# LED.net
KiCad netlist of a schematic drawn in Altium Designer
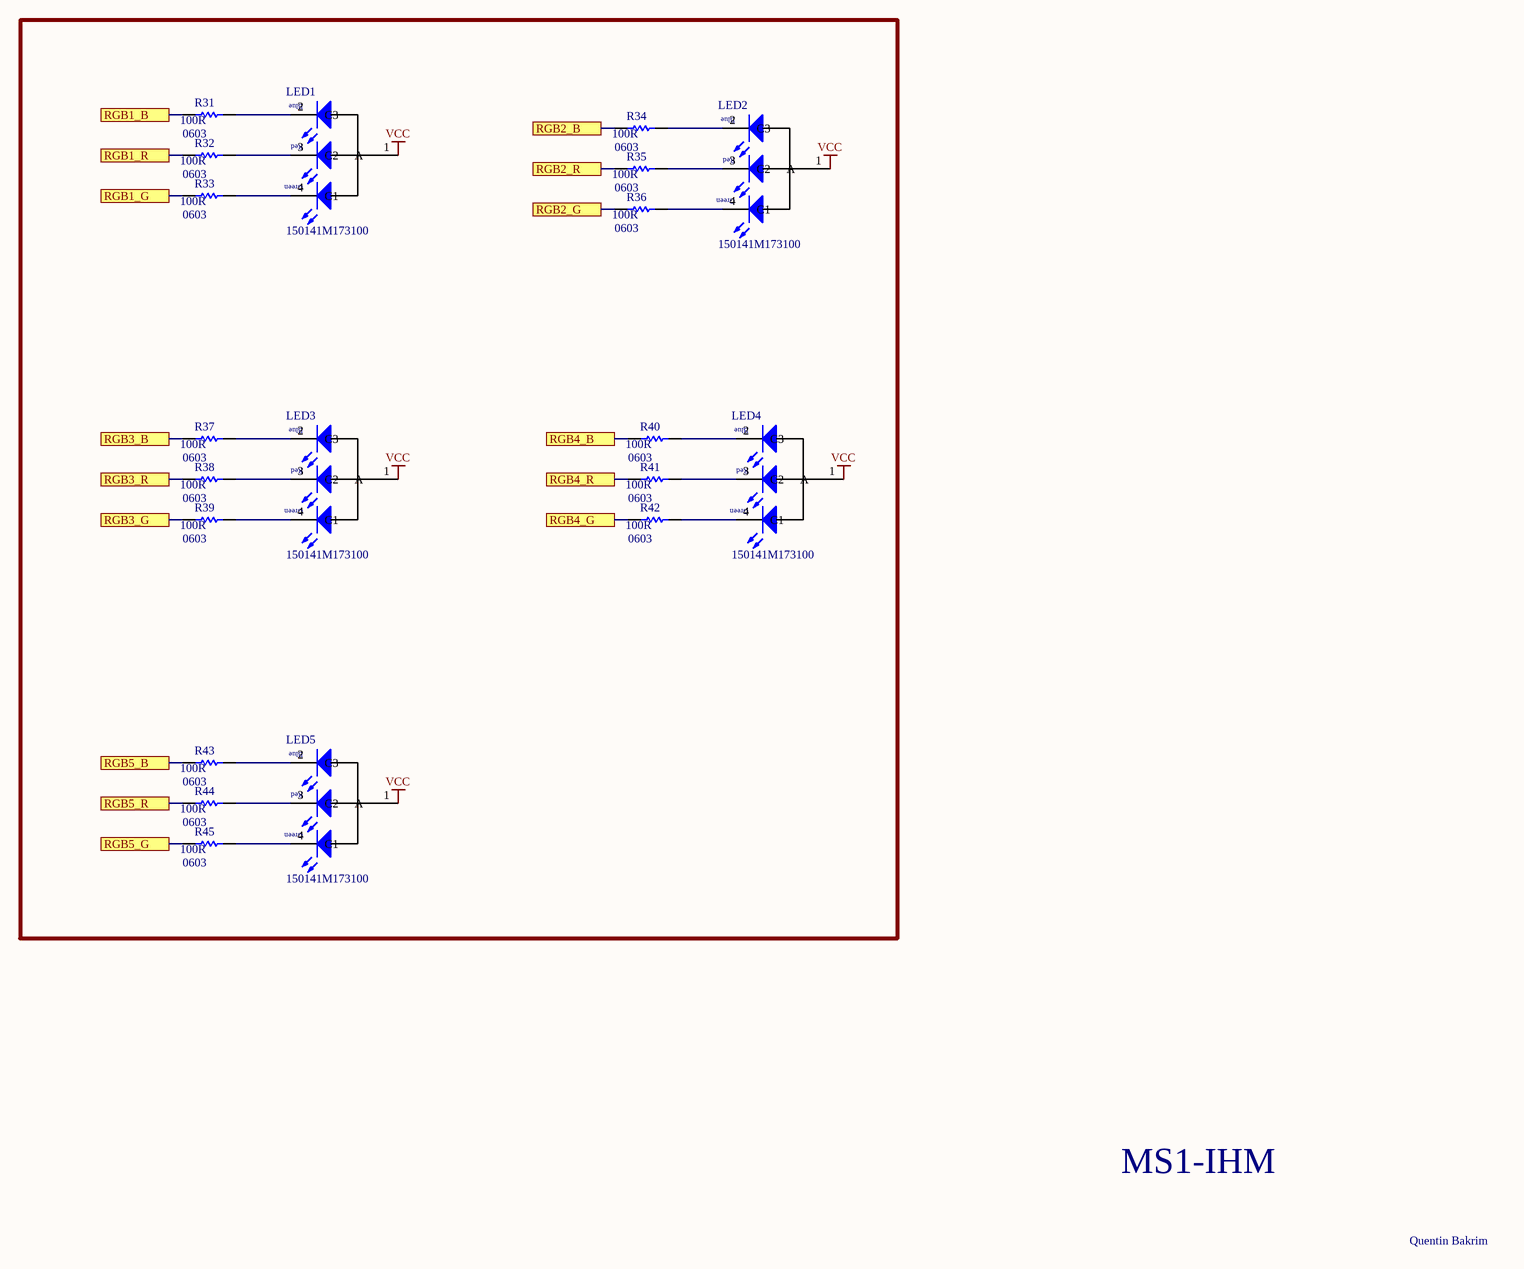
[diagram p0: LED.SchDoc]

(export (version "E")
  (design (tool "Eeschema 10.0.6"))
  (components
    (comp (ref "LED1")
      (value "150141M173100")
      (footprint "3528_A")
      (description "SMD Full-Color Top LED, WL-SFTW, Red & Green & Blue")
      (fields (field (name "MANUFACTURER") "Wuerth Elektronik"))
      (libsource (lib "Altium Content Vault") (part "WE-LED_RGB_A1B2R3G4-4"))
    )
    (comp (ref "LED2")
      (value "150141M173100")
      (footprint "3528_A")
      (description "SMD Full-Color Top LED, WL-SFTW, Red & Green & Blue")
      (fields (field (name "MANUFACTURER") "Wuerth Elektronik"))
      (libsource (lib "Altium Content Vault") (part "WE-LED_RGB_A1B2R3G4-4"))
    )
    (comp (ref "LED3")
      (value "150141M173100")
      (footprint "3528_A")
      (description "SMD Full-Color Top LED, WL-SFTW, Red & Green & Blue")
      (fields (field (name "MANUFACTURER") "Wuerth Elektronik"))
      (libsource (lib "Altium Content Vault") (part "WE-LED_RGB_A1B2R3G4-4"))
    )
    (comp (ref "LED4")
      (value "150141M173100")
      (footprint "3528_A")
      (description "SMD Full-Color Top LED, WL-SFTW, Red & Green & Blue")
      (fields (field (name "MANUFACTURER") "Wuerth Elektronik"))
      (libsource (lib "Altium Content Vault") (part "WE-LED_RGB_A1B2R3G4-4"))
    )
    (comp (ref "LED5")
      (value "150141M173100")
      (footprint "3528_A")
      (description "SMD Full-Color Top LED, WL-SFTW, Red & Green & Blue")
      (fields (field (name "MANUFACTURER") "Wuerth Elektronik"))
      (libsource (lib "Altium Content Vault") (part "WE-LED_RGB_A1B2R3G4-4"))
    )
    (comp (ref "R31")
      (value "ERJ-3EKF1000V")
      (footprint "RESC1608X55X30LL15T15")
      (fields
        (field (name "MANUFACTURER") "Panasonic")
        (field (name "MANUFACTURER PART NUMBER") "ERJ3EKF1000V")
        (field (name "CASE/PACKAGE") "0603")
        (field (name "RESISTANCE") "100R")
        (field (name "TOLERANCE") "1%")
      )
      (libsource (lib "Altium Content Vault") (part "RES"))
    )
    (comp (ref "R32")
      (value "ERJ-3EKF1000V")
      (footprint "RESC1608X55X30LL15T15")
      (fields
        (field (name "MANUFACTURER") "Panasonic")
        (field (name "MANUFACTURER PART NUMBER") "ERJ3EKF1000V")
        (field (name "CASE/PACKAGE") "0603")
        (field (name "RESISTANCE") "100R")
        (field (name "TOLERANCE") "1%")
      )
      (libsource (lib "Altium Content Vault") (part "RES"))
    )
    (comp (ref "R33")
      (value "ERJ-3EKF1000V")
      (footprint "RESC1608X55X30LL15T15")
      (fields
        (field (name "MANUFACTURER") "Panasonic")
        (field (name "MANUFACTURER PART NUMBER") "ERJ3EKF1000V")
        (field (name "CASE/PACKAGE") "0603")
        (field (name "RESISTANCE") "100R")
        (field (name "TOLERANCE") "1%")
      )
      (libsource (lib "Altium Content Vault") (part "RES"))
    )
    (comp (ref "R34")
      (value "ERJ-3EKF1000V")
      (footprint "RESC1608X55X30LL15T15")
      (fields
        (field (name "MANUFACTURER") "Panasonic")
        (field (name "MANUFACTURER PART NUMBER") "ERJ3EKF1000V")
        (field (name "CASE/PACKAGE") "0603")
        (field (name "RESISTANCE") "100R")
        (field (name "TOLERANCE") "1%")
      )
      (libsource (lib "Altium Content Vault") (part "RES"))
    )
    (comp (ref "R35")
      (value "ERJ-3EKF1000V")
      (footprint "RESC1608X55X30LL15T15")
      (fields
        (field (name "MANUFACTURER") "Panasonic")
        (field (name "MANUFACTURER PART NUMBER") "ERJ3EKF1000V")
        (field (name "CASE/PACKAGE") "0603")
        (field (name "RESISTANCE") "100R")
        (field (name "TOLERANCE") "1%")
      )
      (libsource (lib "Altium Content Vault") (part "RES"))
    )
    (comp (ref "R36")
      (value "ERJ-3EKF1000V")
      (footprint "RESC1608X55X30LL15T15")
      (fields
        (field (name "MANUFACTURER") "Panasonic")
        (field (name "MANUFACTURER PART NUMBER") "ERJ3EKF1000V")
        (field (name "CASE/PACKAGE") "0603")
        (field (name "RESISTANCE") "100R")
        (field (name "TOLERANCE") "1%")
      )
      (libsource (lib "Altium Content Vault") (part "RES"))
    )
    (comp (ref "R37")
      (value "ERJ-3EKF1000V")
      (footprint "RESC1608X55X30LL15T15")
      (fields
        (field (name "MANUFACTURER") "Panasonic")
        (field (name "MANUFACTURER PART NUMBER") "ERJ3EKF1000V")
        (field (name "CASE/PACKAGE") "0603")
        (field (name "RESISTANCE") "100R")
        (field (name "TOLERANCE") "1%")
      )
      (libsource (lib "Altium Content Vault") (part "RES"))
    )
    (comp (ref "R38")
      (value "ERJ-3EKF1000V")
      (footprint "RESC1608X55X30LL15T15")
      (fields
        (field (name "MANUFACTURER") "Panasonic")
        (field (name "MANUFACTURER PART NUMBER") "ERJ3EKF1000V")
        (field (name "CASE/PACKAGE") "0603")
        (field (name "RESISTANCE") "100R")
        (field (name "TOLERANCE") "1%")
      )
      (libsource (lib "Altium Content Vault") (part "RES"))
    )
    (comp (ref "R39")
      (value "ERJ-3EKF1000V")
      (footprint "RESC1608X55X30LL15T15")
      (fields
        (field (name "MANUFACTURER") "Panasonic")
        (field (name "MANUFACTURER PART NUMBER") "ERJ3EKF1000V")
        (field (name "CASE/PACKAGE") "0603")
        (field (name "RESISTANCE") "100R")
        (field (name "TOLERANCE") "1%")
      )
      (libsource (lib "Altium Content Vault") (part "RES"))
    )
    (comp (ref "R40")
      (value "ERJ-3EKF1000V")
      (footprint "RESC1608X55X30LL15T15")
      (fields
        (field (name "MANUFACTURER") "Panasonic")
        (field (name "MANUFACTURER PART NUMBER") "ERJ3EKF1000V")
        (field (name "CASE/PACKAGE") "0603")
        (field (name "RESISTANCE") "100R")
        (field (name "TOLERANCE") "1%")
      )
      (libsource (lib "Altium Content Vault") (part "RES"))
    )
    (comp (ref "R41")
      (value "ERJ-3EKF1000V")
      (footprint "RESC1608X55X30LL15T15")
      (fields
        (field (name "MANUFACTURER") "Panasonic")
        (field (name "MANUFACTURER PART NUMBER") "ERJ3EKF1000V")
        (field (name "CASE/PACKAGE") "0603")
        (field (name "RESISTANCE") "100R")
        (field (name "TOLERANCE") "1%")
      )
      (libsource (lib "Altium Content Vault") (part "RES"))
    )
    (comp (ref "R42")
      (value "ERJ-3EKF1000V")
      (footprint "RESC1608X55X30LL15T15")
      (fields
        (field (name "MANUFACTURER") "Panasonic")
        (field (name "MANUFACTURER PART NUMBER") "ERJ3EKF1000V")
        (field (name "CASE/PACKAGE") "0603")
        (field (name "RESISTANCE") "100R")
        (field (name "TOLERANCE") "1%")
      )
      (libsource (lib "Altium Content Vault") (part "RES"))
    )
    (comp (ref "R43")
      (value "ERJ-3EKF1000V")
      (footprint "RESC1608X55X30LL15T15")
      (fields
        (field (name "MANUFACTURER") "Panasonic")
        (field (name "MANUFACTURER PART NUMBER") "ERJ3EKF1000V")
        (field (name "CASE/PACKAGE") "0603")
        (field (name "RESISTANCE") "100R")
        (field (name "TOLERANCE") "1%")
      )
      (libsource (lib "Altium Content Vault") (part "RES"))
    )
    (comp (ref "R44")
      (value "ERJ-3EKF1000V")
      (footprint "RESC1608X55X30LL15T15")
      (fields
        (field (name "MANUFACTURER") "Panasonic")
        (field (name "MANUFACTURER PART NUMBER") "ERJ3EKF1000V")
        (field (name "CASE/PACKAGE") "0603")
        (field (name "RESISTANCE") "100R")
        (field (name "TOLERANCE") "1%")
      )
      (libsource (lib "Altium Content Vault") (part "RES"))
    )
    (comp (ref "R45")
      (value "ERJ-3EKF1000V")
      (footprint "RESC1608X55X30LL15T15")
      (fields
        (field (name "MANUFACTURER") "Panasonic")
        (field (name "MANUFACTURER PART NUMBER") "ERJ3EKF1000V")
        (field (name "CASE/PACKAGE") "0603")
        (field (name "RESISTANCE") "100R")
        (field (name "TOLERANCE") "1%")
      )
      (libsource (lib "Altium Content Vault") (part "RES"))
    )
  )
  (nets
    (net (code "1") (name "/RGB1_B") (class "Default")
      (node (ref "R31") (pin "1") (pinfunction "1_1") (pintype "passive"))
    )
    (net (code "2") (name "/RGB1_G") (class "Default")
      (node (ref "R33") (pin "1") (pinfunction "1_1") (pintype "passive"))
    )
    (net (code "3") (name "/RGB1_R") (class "Default")
      (node (ref "R32") (pin "1") (pinfunction "1_1") (pintype "passive"))
    )
    (net (code "4") (name "/RGB2_B") (class "Default")
      (node (ref "R34") (pin "1") (pinfunction "1_1") (pintype "passive"))
    )
    (net (code "5") (name "/RGB2_G") (class "Default")
      (node (ref "R36") (pin "1") (pinfunction "1_1") (pintype "passive"))
    )
    (net (code "6") (name "/RGB2_R") (class "Default")
      (node (ref "R35") (pin "1") (pinfunction "1_1") (pintype "passive"))
    )
    (net (code "7") (name "/RGB3_B") (class "Default")
      (node (ref "R37") (pin "1") (pinfunction "1_1") (pintype "passive"))
    )
    (net (code "8") (name "/RGB3_G") (class "Default")
      (node (ref "R39") (pin "1") (pinfunction "1_1") (pintype "passive"))
    )
    (net (code "9") (name "/RGB3_R") (class "Default")
      (node (ref "R38") (pin "1") (pinfunction "1_1") (pintype "passive"))
    )
    (net (code "10") (name "/RGB4_B") (class "Default")
      (node (ref "R40") (pin "1") (pinfunction "1_1") (pintype "passive"))
    )
    (net (code "11") (name "/RGB4_G") (class "Default")
      (node (ref "R42") (pin "1") (pinfunction "1_1") (pintype "passive"))
    )
    (net (code "12") (name "/RGB4_R") (class "Default")
      (node (ref "R41") (pin "1") (pinfunction "1_1") (pintype "passive"))
    )
    (net (code "13") (name "/RGB5_B") (class "Default")
      (node (ref "R43") (pin "1") (pinfunction "1_1") (pintype "passive"))
    )
    (net (code "14") (name "/RGB5_G") (class "Default")
      (node (ref "R45") (pin "1") (pinfunction "1_1") (pintype "passive"))
    )
    (net (code "15") (name "/RGB5_R") (class "Default")
      (node (ref "R44") (pin "1") (pinfunction "1_1") (pintype "passive"))
    )
    (net (code "16") (name "Net-(LED1-C1)") (class "Default")
      (node (ref "LED1") (pin "4") (pinfunction "C1_4") (pintype "passive"))
      (node (ref "R33") (pin "2") (pinfunction "2_2") (pintype "passive"))
    )
    (net (code "17") (name "Net-(LED1-C2)") (class "Default")
      (node (ref "LED1") (pin "3") (pinfunction "C2_3") (pintype "passive"))
      (node (ref "R32") (pin "2") (pinfunction "2_2") (pintype "passive"))
    )
    (net (code "18") (name "Net-(LED1-C3)") (class "Default")
      (node (ref "LED1") (pin "2") (pinfunction "C3_2") (pintype "passive"))
      (node (ref "R31") (pin "2") (pinfunction "2_2") (pintype "passive"))
    )
    (net (code "19") (name "Net-(LED2-C1)") (class "Default")
      (node (ref "LED2") (pin "4") (pinfunction "C1_4") (pintype "passive"))
      (node (ref "R36") (pin "2") (pinfunction "2_2") (pintype "passive"))
    )
    (net (code "20") (name "Net-(LED2-C2)") (class "Default")
      (node (ref "LED2") (pin "3") (pinfunction "C2_3") (pintype "passive"))
      (node (ref "R35") (pin "2") (pinfunction "2_2") (pintype "passive"))
    )
    (net (code "21") (name "Net-(LED2-C3)") (class "Default")
      (node (ref "LED2") (pin "2") (pinfunction "C3_2") (pintype "passive"))
      (node (ref "R34") (pin "2") (pinfunction "2_2") (pintype "passive"))
    )
    (net (code "22") (name "Net-(LED3-C1)") (class "Default")
      (node (ref "LED3") (pin "4") (pinfunction "C1_4") (pintype "passive"))
      (node (ref "R39") (pin "2") (pinfunction "2_2") (pintype "passive"))
    )
    (net (code "23") (name "Net-(LED3-C2)") (class "Default")
      (node (ref "LED3") (pin "3") (pinfunction "C2_3") (pintype "passive"))
      (node (ref "R38") (pin "2") (pinfunction "2_2") (pintype "passive"))
    )
    (net (code "24") (name "Net-(LED3-C3)") (class "Default")
      (node (ref "LED3") (pin "2") (pinfunction "C3_2") (pintype "passive"))
      (node (ref "R37") (pin "2") (pinfunction "2_2") (pintype "passive"))
    )
    (net (code "25") (name "Net-(LED4-C1)") (class "Default")
      (node (ref "LED4") (pin "4") (pinfunction "C1_4") (pintype "passive"))
      (node (ref "R42") (pin "2") (pinfunction "2_2") (pintype "passive"))
    )
    (net (code "26") (name "Net-(LED4-C2)") (class "Default")
      (node (ref "LED4") (pin "3") (pinfunction "C2_3") (pintype "passive"))
      (node (ref "R41") (pin "2") (pinfunction "2_2") (pintype "passive"))
    )
    (net (code "27") (name "Net-(LED4-C3)") (class "Default")
      (node (ref "LED4") (pin "2") (pinfunction "C3_2") (pintype "passive"))
      (node (ref "R40") (pin "2") (pinfunction "2_2") (pintype "passive"))
    )
    (net (code "28") (name "Net-(LED5-C1)") (class "Default")
      (node (ref "LED5") (pin "4") (pinfunction "C1_4") (pintype "passive"))
      (node (ref "R45") (pin "2") (pinfunction "2_2") (pintype "passive"))
    )
    (net (code "29") (name "Net-(LED5-C2)") (class "Default")
      (node (ref "LED5") (pin "3") (pinfunction "C2_3") (pintype "passive"))
      (node (ref "R44") (pin "2") (pinfunction "2_2") (pintype "passive"))
    )
    (net (code "30") (name "Net-(LED5-C3)") (class "Default")
      (node (ref "LED5") (pin "2") (pinfunction "C3_2") (pintype "passive"))
      (node (ref "R43") (pin "2") (pinfunction "2_2") (pintype "passive"))
    )
    (net (code "31") (name "VCC") (class "Default")
      (node (ref "LED1") (pin "1") (pinfunction "A_1") (pintype "passive"))
      (node (ref "LED2") (pin "1") (pinfunction "A_1") (pintype "passive"))
      (node (ref "LED3") (pin "1") (pinfunction "A_1") (pintype "passive"))
      (node (ref "LED4") (pin "1") (pinfunction "A_1") (pintype "passive"))
      (node (ref "LED5") (pin "1") (pinfunction "A_1") (pintype "passive"))
    )
  )
)
